# DAQ_IO.net
KiCad netlist of a schematic drawn in Altium Designer
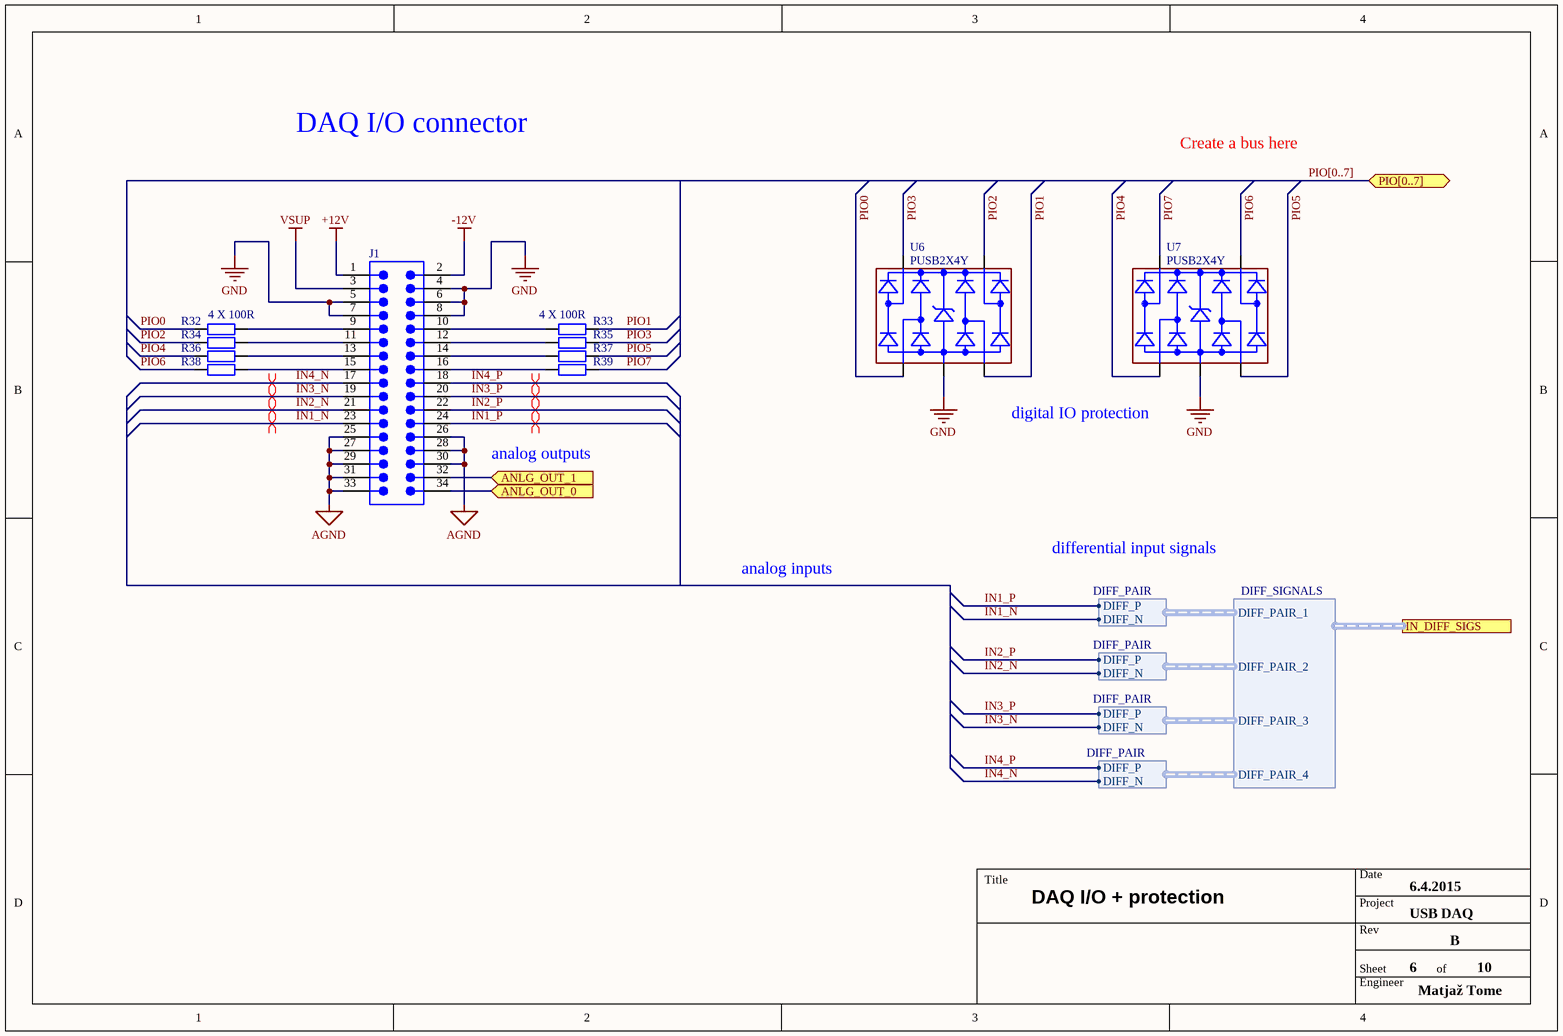
[diagram p0: DAQ_IO.SchDoc]

(export (version "E")
  (design (tool "Eeschema 10.0.6"))
  (components
    (comp (ref "J1")
      (value "2X17")
      (footprint "IDC34R")
      (description "Pin Header, Right Angle, Wire-to-Board, 2.54 mm, 2 Rows, 34 Contacts, Through Hole Right Angle")
      (fields (field (name "MANUFACTURER") "Harting"))
      (libsource (lib "DAQ_REV_B") (part "09 18 534 7323"))
    )
    (comp (ref "R32")
      (value "100R")
      (footprint "R_0603")
      (description "Generic resistor")
      (libsource (lib "DAQ_REV_B") (part "Resistor"))
    )
    (comp (ref "R33")
      (value "100R")
      (footprint "R_0603")
      (description "Generic resistor")
      (libsource (lib "DAQ_REV_B") (part "Resistor"))
    )
    (comp (ref "R34")
      (value "100R")
      (footprint "R_0603")
      (description "Generic resistor")
      (libsource (lib "DAQ_REV_B") (part "Resistor"))
    )
    (comp (ref "R35")
      (value "100R")
      (footprint "R_0603")
      (description "Generic resistor")
      (libsource (lib "DAQ_REV_B") (part "Resistor"))
    )
    (comp (ref "R36")
      (value "100R")
      (footprint "R_0603")
      (description "Generic resistor")
      (libsource (lib "DAQ_REV_B") (part "Resistor"))
    )
    (comp (ref "R37")
      (value "100R")
      (footprint "R_0603")
      (description "Generic resistor")
      (libsource (lib "DAQ_REV_B") (part "Resistor"))
    )
    (comp (ref "R38")
      (value "100R")
      (footprint "R_0603")
      (description "Generic resistor")
      (libsource (lib "DAQ_REV_B") (part "Resistor"))
    )
    (comp (ref "R39")
      (value "100R")
      (footprint "R_0603")
      (description "Generic resistor")
      (libsource (lib "DAQ_REV_B") (part "Resistor"))
    )
    (comp (ref "U6")
      (value "PUSB2X4Y")
      (footprint "SOT363")
      (description "ESD protection for high-speed interfaces")
      (fields (field (name "PART NUMBER") "XDE0000") (field (name "MANUFACTURER") "Multicomp"))
      (libsource (lib "DAQ_REV_B") (part "PUSB2X4Y"))
    )
    (comp (ref "U7")
      (value "PUSB2X4Y")
      (footprint "SOT363")
      (description "ESD protection for high-speed interfaces")
      (fields (field (name "PART NUMBER") "XDE0000") (field (name "MANUFACTURER") "Multicomp"))
      (libsource (lib "DAQ_REV_B") (part "PUSB2X4Y"))
    )
  )
  (nets
    (net (code "3") (name "+12V") (class "Default")
      (node (ref "J1") (pin "1") (pinfunction "1_1") (pintype "passive"))
    )
    (net (code "4") (name "-12V") (class "Default")
      (node (ref "J1") (pin "2") (pinfunction "2_2") (pintype "passive"))
    )
    (net (code "5") (name "/ANLG_OUT_0") (class "Default")
      (node (ref "J1") (pin "34") (pinfunction "34_34") (pintype "passive"))
    )
    (net (code "6") (name "/ANLG_OUT_1") (class "Default")
      (node (ref "J1") (pin "32") (pinfunction "32_32") (pintype "passive"))
    )
    (net (code "7") (name "/IN1_N") (class "Default")
      (node (ref "J1") (pin "23") (pinfunction "23_23") (pintype "passive"))
    )
    (net (code "8") (name "/IN1_P") (class "Default")
      (node (ref "J1") (pin "24") (pinfunction "24_24") (pintype "passive"))
    )
    (net (code "9") (name "/IN2_N") (class "Default")
      (node (ref "J1") (pin "21") (pinfunction "21_21") (pintype "passive"))
    )
    (net (code "10") (name "/IN2_P") (class "Default")
      (node (ref "J1") (pin "22") (pinfunction "22_22") (pintype "passive"))
    )
    (net (code "11") (name "/IN3_N") (class "Default")
      (node (ref "J1") (pin "19") (pinfunction "19_19") (pintype "passive"))
    )
    (net (code "12") (name "/IN3_P") (class "Default")
      (node (ref "J1") (pin "20") (pinfunction "20_20") (pintype "passive"))
    )
    (net (code "13") (name "/IN4_N") (class "Default")
      (node (ref "J1") (pin "17") (pinfunction "17_17") (pintype "passive"))
    )
    (net (code "14") (name "/IN4_P") (class "Default")
      (node (ref "J1") (pin "18") (pinfunction "18_18") (pintype "passive"))
    )
    (net (code "16") (name "/PIO0") (class "Default")
      (node (ref "R32") (pin "1") (pintype "passive"))
      (node (ref "U6") (pin "1") (pinfunction "1_1") (pintype "passive"))
    )
    (net (code "17") (name "/PIO1") (class "Default")
      (node (ref "R33") (pin "2") (pintype "passive"))
      (node (ref "U6") (pin "3") (pinfunction "3_3") (pintype "passive"))
    )
    (net (code "18") (name "/PIO2") (class "Default")
      (node (ref "R34") (pin "1") (pintype "passive"))
      (node (ref "U6") (pin "4") (pinfunction "4_4") (pintype "passive"))
    )
    (net (code "19") (name "/PIO3") (class "Default")
      (node (ref "R35") (pin "2") (pintype "passive"))
      (node (ref "U6") (pin "6") (pinfunction "6_6") (pintype "passive"))
    )
    (net (code "20") (name "/PIO4") (class "Default")
      (node (ref "R36") (pin "1") (pintype "passive"))
      (node (ref "U7") (pin "1") (pinfunction "1_1") (pintype "passive"))
    )
    (net (code "21") (name "/PIO5") (class "Default")
      (node (ref "R37") (pin "2") (pintype "passive"))
      (node (ref "U7") (pin "3") (pinfunction "3_3") (pintype "passive"))
    )
    (net (code "22") (name "/PIO6") (class "Default")
      (node (ref "R38") (pin "1") (pintype "passive"))
      (node (ref "U7") (pin "4") (pinfunction "4_4") (pintype "passive"))
    )
    (net (code "23") (name "/PIO7") (class "Default")
      (node (ref "R39") (pin "2") (pintype "passive"))
      (node (ref "U7") (pin "6") (pinfunction "6_6") (pintype "passive"))
    )
    (net (code "26") (name "AGND") (class "Default")
      (node (ref "J1") (pin "25") (pinfunction "25_25") (pintype "passive"))
      (node (ref "J1") (pin "26") (pinfunction "26_26") (pintype "passive"))
      (node (ref "J1") (pin "27") (pinfunction "27_27") (pintype "passive"))
      (node (ref "J1") (pin "28") (pinfunction "28_28") (pintype "passive"))
      (node (ref "J1") (pin "29") (pinfunction "29_29") (pintype "passive"))
      (node (ref "J1") (pin "30") (pinfunction "30_30") (pintype "passive"))
      (node (ref "J1") (pin "31") (pinfunction "31_31") (pintype "passive"))
      (node (ref "J1") (pin "33") (pinfunction "33_33") (pintype "passive"))
    )
    (net (code "27") (name "GND") (class "Default")
      (node (ref "J1") (pin "4") (pinfunction "4_4") (pintype "passive"))
      (node (ref "J1") (pin "5") (pinfunction "5_5") (pintype "passive"))
      (node (ref "J1") (pin "6") (pinfunction "6_6") (pintype "passive"))
      (node (ref "J1") (pin "7") (pinfunction "7_7") (pintype "passive"))
      (node (ref "J1") (pin "8") (pinfunction "8_8") (pintype "passive"))
      (node (ref "U6") (pin "2") (pinfunction "2_2") (pintype "passive"))
      (node (ref "U7") (pin "2") (pinfunction "2_2") (pintype "passive"))
    )
    (net (code "28") (name "Net-(J1-Pad9)") (class "Default")
      (node (ref "J1") (pin "9") (pinfunction "9_9") (pintype "passive"))
      (node (ref "R32") (pin "2") (pintype "passive"))
    )
    (net (code "29") (name "Net-(J1-Pad10)") (class "Default")
      (node (ref "J1") (pin "10") (pinfunction "10_10") (pintype "passive"))
      (node (ref "R33") (pin "1") (pintype "passive"))
    )
    (net (code "30") (name "Net-(J1-Pad11)") (class "Default")
      (node (ref "J1") (pin "11") (pinfunction "11_11") (pintype "passive"))
      (node (ref "R34") (pin "2") (pintype "passive"))
    )
    (net (code "31") (name "Net-(J1-Pad12)") (class "Default")
      (node (ref "J1") (pin "12") (pinfunction "12_12") (pintype "passive"))
      (node (ref "R35") (pin "1") (pintype "passive"))
    )
    (net (code "32") (name "Net-(J1-Pad13)") (class "Default")
      (node (ref "J1") (pin "13") (pinfunction "13_13") (pintype "passive"))
      (node (ref "R36") (pin "2") (pintype "passive"))
    )
    (net (code "33") (name "Net-(J1-Pad14)") (class "Default")
      (node (ref "J1") (pin "14") (pinfunction "14_14") (pintype "passive"))
      (node (ref "R37") (pin "1") (pintype "passive"))
    )
    (net (code "34") (name "Net-(J1-Pad15)") (class "Default")
      (node (ref "J1") (pin "15") (pinfunction "15_15") (pintype "passive"))
      (node (ref "R38") (pin "2") (pintype "passive"))
    )
    (net (code "35") (name "Net-(J1-Pad16)") (class "Default")
      (node (ref "J1") (pin "16") (pinfunction "16_16") (pintype "passive"))
      (node (ref "R39") (pin "1") (pintype "passive"))
    )
    (net (code "36") (name "VSUP") (class "Default")
      (node (ref "J1") (pin "3") (pinfunction "3_3") (pintype "passive"))
    )
  )
)
